# TestA.net
KiCad netlist of a schematic drawn in EAGLE
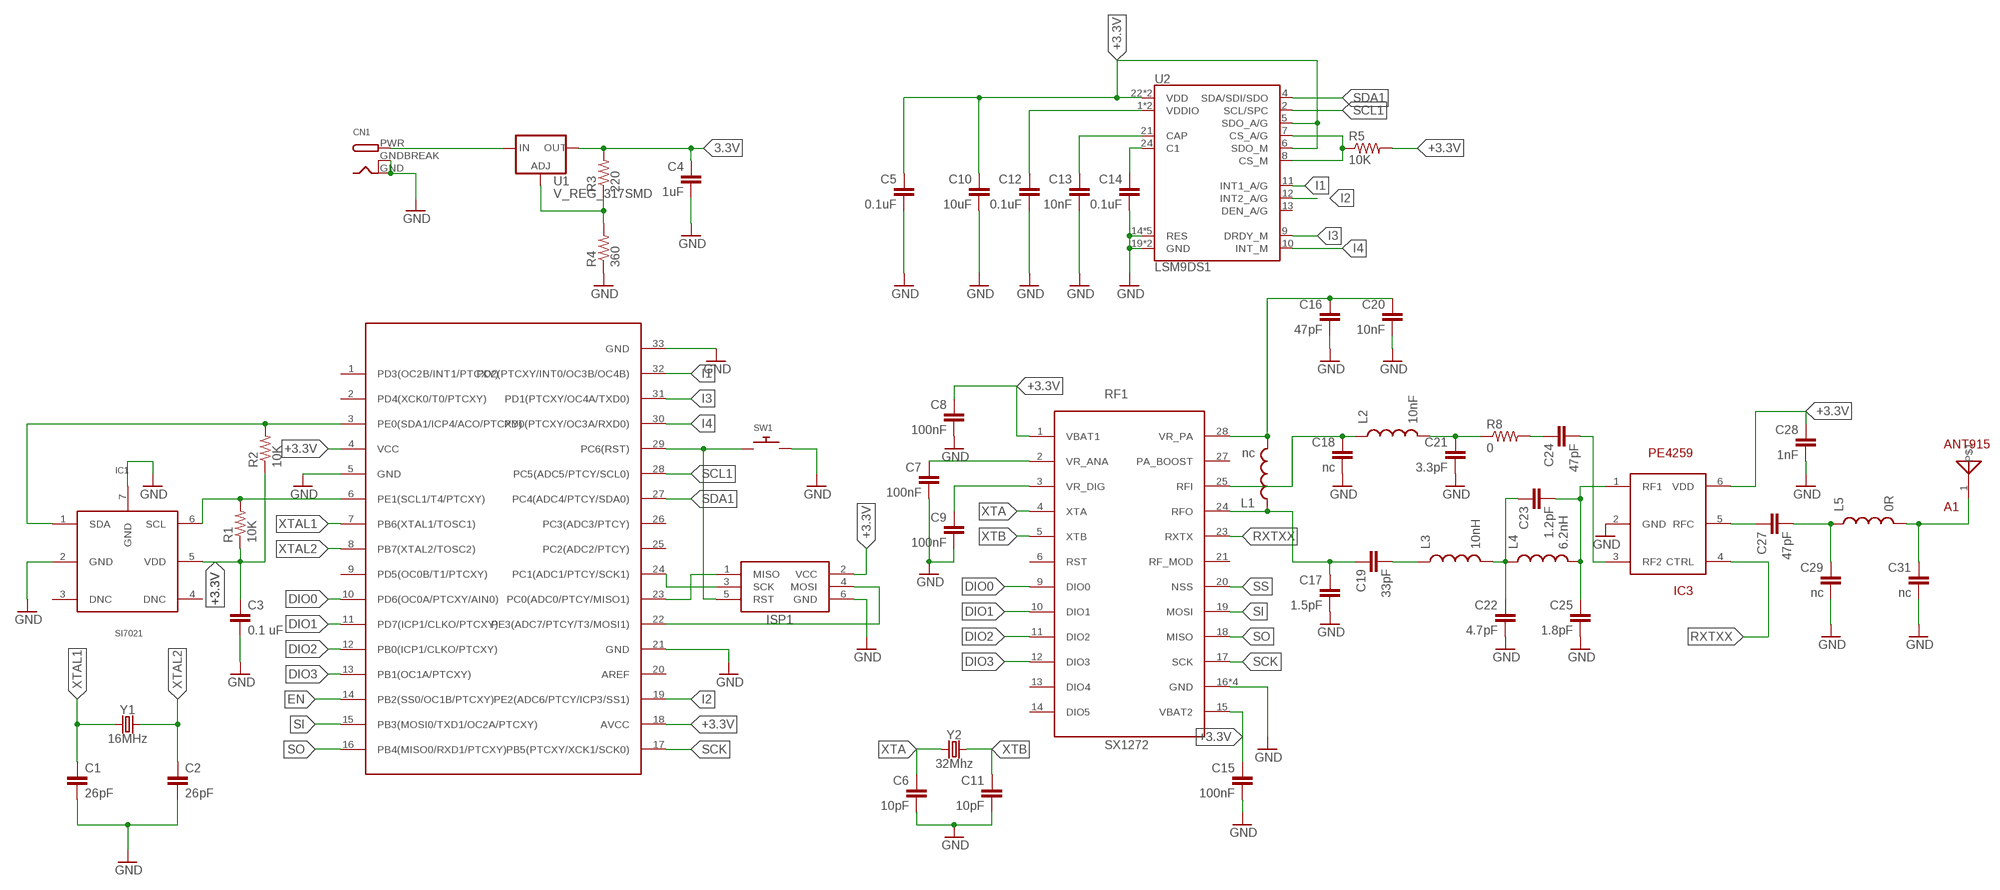
[diagram p0: schematic, sheet 1]

(export (version "E")
  (design (tool "Eeschema 10.0.6"))
  (components
    (comp (ref "A1")
      (value "ANT915")
      (footprint "eagle-import:ANT915")
      (libsource (lib "eagle-import") (part "ANT915"))
    )
    (comp (ref "C1")
      (value "26pF")
      (footprint "eagle-import:0402-CAP")
      (libsource (lib "eagle-import") (part "CAP0402-CAP"))
    )
    (comp (ref "C2")
      (value "26pF")
      (footprint "eagle-import:0402-CAP")
      (libsource (lib "eagle-import") (part "CAP0402-CAP"))
    )
    (comp (ref "C3")
      (value "0.1 uF")
      (footprint "eagle-import:0402-CAP")
      (libsource (lib "eagle-import") (part "CAP0402-CAP"))
    )
    (comp (ref "C4")
      (value "1uF")
      (footprint "eagle-import:0402-CAP")
      (libsource (lib "eagle-import") (part "CAP0402-CAP"))
    )
    (comp (ref "C5")
      (value "0.1uF")
      (footprint "eagle-import:0402-CAP")
      (libsource (lib "eagle-import") (part "CAP0402-CAP"))
    )
    (comp (ref "C6")
      (value "10pF")
      (footprint "eagle-import:0402-CAP")
      (libsource (lib "eagle-import") (part "CAP0402-CAP"))
    )
    (comp (ref "C7")
      (value "100nF")
      (footprint "eagle-import:0402-CAP")
      (libsource (lib "eagle-import") (part "CAP0402-CAP"))
    )
    (comp (ref "C8")
      (value "100nF")
      (footprint "eagle-import:0402-CAP")
      (libsource (lib "eagle-import") (part "CAP0402-CAP"))
    )
    (comp (ref "C9")
      (value "100nF")
      (footprint "eagle-import:0402-CAP")
      (libsource (lib "eagle-import") (part "CAP0402-CAP"))
    )
    (comp (ref "C10")
      (value "10uF")
      (footprint "eagle-import:0402-CAP")
      (libsource (lib "eagle-import") (part "CAP0402-CAP"))
    )
    (comp (ref "C11")
      (value "10pF")
      (footprint "eagle-import:0402-CAP")
      (libsource (lib "eagle-import") (part "CAP0402-CAP"))
    )
    (comp (ref "C12")
      (value "0.1uF")
      (footprint "eagle-import:0402-CAP")
      (libsource (lib "eagle-import") (part "CAP0402-CAP"))
    )
    (comp (ref "C13")
      (value "10nF")
      (footprint "eagle-import:0402-CAP")
      (libsource (lib "eagle-import") (part "CAP0402-CAP"))
    )
    (comp (ref "C14")
      (value "0.1uF")
      (footprint "eagle-import:0402-CAP")
      (libsource (lib "eagle-import") (part "CAP0402-CAP"))
    )
    (comp (ref "C15")
      (value "100nF")
      (footprint "eagle-import:0402-CAP")
      (libsource (lib "eagle-import") (part "CAP0402-CAP"))
    )
    (comp (ref "C16")
      (value "47pF")
      (footprint "eagle-import:0402-CAP")
      (libsource (lib "eagle-import") (part "CAP0402-CAP"))
    )
    (comp (ref "C17")
      (value "1.5pF")
      (footprint "eagle-import:0402-CAP")
      (libsource (lib "eagle-import") (part "CAP0402-CAP"))
    )
    (comp (ref "C18")
      (value "nc")
      (footprint "eagle-import:0402-CAP")
      (libsource (lib "eagle-import") (part "CAP0402-CAP"))
    )
    (comp (ref "C19")
      (value "33pF")
      (footprint "eagle-import:0402-CAP")
      (libsource (lib "eagle-import") (part "CAP0402-CAP"))
    )
    (comp (ref "C20")
      (value "10nF")
      (footprint "eagle-import:0402-CAP")
      (libsource (lib "eagle-import") (part "CAP0402-CAP"))
    )
    (comp (ref "C21")
      (value "3.3pF")
      (footprint "eagle-import:0402-CAP")
      (libsource (lib "eagle-import") (part "CAP0402-CAP"))
    )
    (comp (ref "C22")
      (value "4.7pF")
      (footprint "eagle-import:0402-CAP")
      (libsource (lib "eagle-import") (part "CAP0402-CAP"))
    )
    (comp (ref "C23")
      (value "1.2pF")
      (footprint "eagle-import:0402-CAP")
      (libsource (lib "eagle-import") (part "CAP0402-CAP"))
    )
    (comp (ref "C24")
      (value "47pF")
      (footprint "eagle-import:0402-CAP")
      (libsource (lib "eagle-import") (part "CAP0402-CAP"))
    )
    (comp (ref "C25")
      (value "1.8pF")
      (footprint "eagle-import:0402-CAP")
      (libsource (lib "eagle-import") (part "CAP0402-CAP"))
    )
    (comp (ref "C27")
      (value "47pF")
      (footprint "eagle-import:0402-CAP")
      (libsource (lib "eagle-import") (part "CAP0402-CAP"))
    )
    (comp (ref "C28")
      (value "1nF")
      (footprint "eagle-import:0402-CAP")
      (libsource (lib "eagle-import") (part "CAP0402-CAP"))
    )
    (comp (ref "C29")
      (value "nc")
      (footprint "eagle-import:0402-CAP")
      (libsource (lib "eagle-import") (part "CAP0402-CAP"))
    )
    (comp (ref "C31")
      (value "nc")
      (footprint "eagle-import:0402-CAP")
      (libsource (lib "eagle-import") (part "CAP0402-CAP"))
    )
    (comp (ref "CN1")
      (value "DCBARRELPTH")
      (footprint "eagle-import:DCJACK_2MM_PTH")
      (libsource (lib "eagle-import") (part "DCBARRELPTH"))
    )
    (comp (ref "IC1")
      (value "SI7021")
      (footprint "eagle-import:SI7021")
      (libsource (lib "eagle-import") (part "SI7021"))
    )
    (comp (ref "IC2")
      (value "ATMEGA328-PB")
      (footprint "eagle-import:ATMEGA328-PB")
      (libsource (lib "eagle-import") (part "ATMEGA328-PB"))
    )
    (comp (ref "IC3")
      (value "PE4259")
      (footprint "eagle-import:PE4259")
      (libsource (lib "eagle-import") (part "PE4259"))
    )
    (comp (ref "ISP1")
      (value "AVRISP-6")
      (footprint "eagle-import:AVRISP")
      (libsource (lib "eagle-import") (part "AVRISP-6"))
    )
    (comp (ref "L1")
      (value "nc")
      (footprint "eagle-import:C0402")
      (libsource (lib "eagle-import") (part "INDUCTOR0402"))
    )
    (comp (ref "L2")
      (value "10nF")
      (footprint "eagle-import:C0402")
      (libsource (lib "eagle-import") (part "INDUCTOR0402"))
    )
    (comp (ref "L3")
      (value "10nH")
      (footprint "eagle-import:C0402")
      (libsource (lib "eagle-import") (part "INDUCTOR0402"))
    )
    (comp (ref "L4")
      (value "6.2nH")
      (footprint "eagle-import:C0402")
      (libsource (lib "eagle-import") (part "INDUCTOR0402"))
    )
    (comp (ref "L5")
      (value "0R")
      (footprint "eagle-import:C0402")
      (libsource (lib "eagle-import") (part "INDUCTOR0402"))
    )
    (comp (ref "R1")
      (value "10K")
      (footprint "eagle-import:0402-RES")
      (libsource (lib "eagle-import") (part "RESISTOR0402-RES"))
    )
    (comp (ref "R2")
      (value "10K")
      (footprint "eagle-import:0402-RES")
      (libsource (lib "eagle-import") (part "RESISTOR0402-RES"))
    )
    (comp (ref "R3")
      (value "220")
      (footprint "eagle-import:0402-RES")
      (libsource (lib "eagle-import") (part "RESISTOR0402-RES"))
    )
    (comp (ref "R4")
      (value "360")
      (footprint "eagle-import:0402-RES")
      (libsource (lib "eagle-import") (part "RESISTOR0402-RES"))
    )
    (comp (ref "R5")
      (value "10K")
      (footprint "eagle-import:0402-RES")
      (libsource (lib "eagle-import") (part "RESISTOR0402-RES"))
    )
    (comp (ref "R8")
      (value "0")
      (footprint "eagle-import:0402-RES")
      (libsource (lib "eagle-import") (part "RESISTOR0402-RES"))
    )
    (comp (ref "RF1")
      (value "SX1272")
      (footprint "eagle-import:SX1272")
      (libsource (lib "eagle-import") (part "SX1272"))
    )
    (comp (ref "SW1")
      (value "SWITCH_PUSHBUTTONSOFTTOUCHSMD_SJ")
      (footprint "eagle-import:PUSHBUTTON_SMD_SJ")
      (libsource (lib "eagle-import") (part "SWITCH_PUSHBUTTONSOFTTOUCHSMD_SJ"))
    )
    (comp (ref "U1")
      (value "V_REG_317SMD")
      (footprint "eagle-import:SOT223")
      (libsource (lib "eagle-import") (part "V_REG_317SMD"))
    )
    (comp (ref "U2")
      (value "LSM9DS1")
      (footprint "eagle-import:LGA24-8X4")
      (libsource (lib "eagle-import") (part "LSM9DS1"))
    )
    (comp (ref "Y1")
      (value "16MHz")
      (footprint "eagle-import:CRYSTAL-SMD-2.0X1.6MM")
      (libsource (lib "eagle-import") (part "CRYSTAL-16MHZSMD-2X1.6"))
    )
    (comp (ref "Y2")
      (value "32Mhz")
      (footprint "eagle-import:CRYSTAL-SMD-2.0X1.6MM")
      (libsource (lib "eagle-import") (part "CRYSTAL-16MHZSMD-2X1.6"))
    )
  )
  (nets
    (net (code "1") (name "+3.3V") (class "Default")
      (node (ref "C10") (pin "1") (pinfunction "1_1") (pintype "passive"))
      (node (ref "C15") (pin "1") (pinfunction "1_1") (pintype "passive"))
      (node (ref "C28") (pin "1") (pinfunction "1_1") (pintype "passive"))
      (node (ref "C3") (pin "1") (pinfunction "1_1") (pintype "passive"))
      (node (ref "C5") (pin "1") (pinfunction "1_1") (pintype "passive"))
      (node (ref "C8") (pin "1") (pinfunction "1_1") (pintype "passive"))
      (node (ref "IC1") (pin "5") (pinfunction "VDD_5") (pintype "bidirectional"))
      (node (ref "IC2") (pin "18") (pinfunction "AVCC_18") (pintype "bidirectional"))
      (node (ref "IC2") (pin "4") (pinfunction "VCC_4") (pintype "bidirectional"))
      (node (ref "IC3") (pin "6") (pinfunction "VDD_6") (pintype "bidirectional"))
      (node (ref "ISP1") (pin "2") (pinfunction "VCC_2") (pintype "power_in"))
      (node (ref "R1") (pin "1") (pinfunction "1_1") (pintype "passive"))
      (node (ref "R2") (pin "1") (pinfunction "1_1") (pintype "passive"))
      (node (ref "R5") (pin "2") (pinfunction "2_2") (pintype "passive"))
      (node (ref "RF1") (pin "1") (pinfunction "VBAT1_1") (pintype "bidirectional"))
      (node (ref "RF1") (pin "15") (pinfunction "VBAT2_15") (pintype "bidirectional"))
      (node (ref "U2") (pin "22") (pinfunction "VDD_22") (pintype "bidirectional"))
      (node (ref "U2") (pin "23") (pinfunction "VDD_23") (pintype "bidirectional"))
      (node (ref "U2") (pin "5") (pinfunction "SDO_A/G_5") (pintype "bidirectional"))
      (node (ref "U2") (pin "6") (pinfunction "SDO_M_6") (pintype "bidirectional"))
    )
    (net (code "2") (name "3.3V") (class "Default")
      (node (ref "C4") (pin "1") (pinfunction "1_1") (pintype "passive"))
      (node (ref "R3") (pin "2") (pinfunction "2_2") (pintype "passive"))
      (node (ref "U1") (pin "2") (pinfunction "OUT_2") (pintype "output"))
    )
    (net (code "3") (name "DIO0") (class "Default")
      (node (ref "IC2") (pin "10") (pinfunction "PD6(OC0A/PTCXY/AIN0)_10") (pintype "bidirectional"))
      (node (ref "RF1") (pin "9") (pinfunction "DIO0_9") (pintype "bidirectional"))
    )
    (net (code "4") (name "DIO1") (class "Default")
      (node (ref "IC2") (pin "11") (pinfunction "PD7(ICP1/CLKO/PTCXY)_11") (pintype "bidirectional"))
      (node (ref "RF1") (pin "10") (pinfunction "DIO1_10") (pintype "bidirectional"))
    )
    (net (code "5") (name "DIO2") (class "Default")
      (node (ref "IC2") (pin "12") (pinfunction "PB0(ICP1/CLKO/PTCXY)_12") (pintype "bidirectional"))
      (node (ref "RF1") (pin "11") (pinfunction "DIO2_11") (pintype "bidirectional"))
    )
    (net (code "6") (name "DIO3") (class "Default")
      (node (ref "IC2") (pin "13") (pinfunction "PB1(OC1A/PTCXY)_13") (pintype "bidirectional"))
      (node (ref "RF1") (pin "12") (pinfunction "DIO3_12") (pintype "bidirectional"))
    )
    (net (code "7") (name "EN") (class "Default")
      (node (ref "IC2") (pin "14") (pinfunction "PB2(SS0/OC1B/PTCXY)_14") (pintype "bidirectional"))
    )
    (net (code "8") (name "GND") (class "Default")
      (node (ref "C1") (pin "2") (pinfunction "2_2") (pintype "passive"))
      (node (ref "C10") (pin "2") (pinfunction "2_2") (pintype "passive"))
      (node (ref "C11") (pin "2") (pinfunction "2_2") (pintype "passive"))
      (node (ref "C12") (pin "2") (pinfunction "2_2") (pintype "passive"))
      (node (ref "C13") (pin "2") (pinfunction "2_2") (pintype "passive"))
      (node (ref "C14") (pin "2") (pinfunction "2_2") (pintype "passive"))
      (node (ref "C15") (pin "2") (pinfunction "2_2") (pintype "passive"))
      (node (ref "C16") (pin "2") (pinfunction "2_2") (pintype "passive"))
      (node (ref "C17") (pin "2") (pinfunction "2_2") (pintype "passive"))
      (node (ref "C18") (pin "2") (pinfunction "2_2") (pintype "passive"))
      (node (ref "C2") (pin "2") (pinfunction "2_2") (pintype "passive"))
      (node (ref "C20") (pin "2") (pinfunction "2_2") (pintype "passive"))
      (node (ref "C21") (pin "2") (pinfunction "2_2") (pintype "passive"))
      (node (ref "C22") (pin "2") (pinfunction "2_2") (pintype "passive"))
      (node (ref "C25") (pin "2") (pinfunction "2_2") (pintype "passive"))
      (node (ref "C28") (pin "2") (pinfunction "2_2") (pintype "passive"))
      (node (ref "C29") (pin "2") (pinfunction "2_2") (pintype "passive"))
      (node (ref "C3") (pin "2") (pinfunction "2_2") (pintype "passive"))
      (node (ref "C31") (pin "2") (pinfunction "2_2") (pintype "passive"))
      (node (ref "C4") (pin "2") (pinfunction "2_2") (pintype "passive"))
      (node (ref "C5") (pin "2") (pinfunction "2_2") (pintype "passive"))
      (node (ref "C6") (pin "2") (pinfunction "2_2") (pintype "passive"))
      (node (ref "C7") (pin "2") (pinfunction "2_2") (pintype "passive"))
      (node (ref "C8") (pin "2") (pinfunction "2_2") (pintype "passive"))
      (node (ref "C9") (pin "2") (pinfunction "2_2") (pintype "passive"))
      (node (ref "CN1") (pin "GND") (pinfunction "GND_GND") (pintype "power_in"))
      (node (ref "CN1") (pin "GNDBREAK") (pinfunction "GNDBREAK_GNDBREAK") (pintype "power_in"))
      (node (ref "IC1") (pin "2") (pinfunction "GND_2") (pintype "bidirectional"))
      (node (ref "IC1") (pin "7") (pinfunction "GND_7") (pintype "bidirectional"))
      (node (ref "IC2") (pin "21") (pinfunction "GND_21") (pintype "bidirectional"))
      (node (ref "IC2") (pin "33") (pinfunction "GND_33") (pintype "bidirectional"))
      (node (ref "IC2") (pin "5") (pinfunction "GND_5") (pintype "bidirectional"))
      (node (ref "IC3") (pin "2") (pinfunction "GND_2") (pintype "bidirectional"))
      (node (ref "ISP1") (pin "6") (pinfunction "GND_6") (pintype "power_in"))
      (node (ref "R4") (pin "1") (pinfunction "1_1") (pintype "passive"))
      (node (ref "RF1") (pin "16") (pinfunction "GND_16") (pintype "bidirectional"))
      (node (ref "RF1") (pin "22") (pinfunction "GND_22") (pintype "bidirectional"))
      (node (ref "RF1") (pin "26") (pinfunction "GND_26") (pintype "bidirectional"))
      (node (ref "RF1") (pin "29") (pinfunction "GND_29") (pintype "bidirectional"))
      (node (ref "SW1") (pin "P$2") (pinfunction "P$2_P$2") (pintype "passive"))
      (node (ref "U2") (pin "14") (pinfunction "RES_14") (pintype "bidirectional"))
      (node (ref "U2") (pin "15") (pinfunction "RES_15") (pintype "bidirectional"))
      (node (ref "U2") (pin "16") (pinfunction "RES_16") (pintype "bidirectional"))
      (node (ref "U2") (pin "17") (pinfunction "RES_17") (pintype "bidirectional"))
      (node (ref "U2") (pin "18") (pinfunction "RES_18") (pintype "bidirectional"))
      (node (ref "U2") (pin "19") (pinfunction "GND_19") (pintype "bidirectional"))
      (node (ref "U2") (pin "20") (pinfunction "GND_20") (pintype "bidirectional"))
    )
    (net (code "9") (name "I1") (class "Default")
      (node (ref "IC2") (pin "32") (pinfunction "PD2(PTCXY/INT0/OC3B/OC4B)_32") (pintype "bidirectional"))
      (node (ref "U2") (pin "11") (pinfunction "INT1_A/G_11") (pintype "bidirectional"))
    )
    (net (code "10") (name "I2") (class "Default")
      (node (ref "IC2") (pin "19") (pinfunction "PE2(ADC6/PTCY/ICP3/SS1)_19") (pintype "bidirectional"))
      (node (ref "U2") (pin "12") (pinfunction "INT2_A/G_12") (pintype "bidirectional"))
    )
    (net (code "11") (name "I3") (class "Default")
      (node (ref "IC2") (pin "31") (pinfunction "PD1(PTCXY/OC4A/TXD0)_31") (pintype "bidirectional"))
      (node (ref "U2") (pin "9") (pinfunction "DRDY_M_9") (pintype "bidirectional"))
    )
    (net (code "12") (name "I4") (class "Default")
      (node (ref "IC2") (pin "30") (pinfunction "PD0(PTCXY/OC3A/RXD0)_30") (pintype "bidirectional"))
      (node (ref "U2") (pin "10") (pinfunction "INT_M_10") (pintype "bidirectional"))
    )
    (net (code "13") (name "Net-(A1-P$1)") (class "Default")
      (node (ref "A1") (pin "1") (pinfunction "P$1_1") (pintype "bidirectional"))
      (node (ref "C31") (pin "1") (pinfunction "1_1") (pintype "passive"))
      (node (ref "L5") (pin "2") (pinfunction "2_2") (pintype "passive"))
    )
    (net (code "14") (name "Net-(C12-Pad1)") (class "Default")
      (node (ref "C12") (pin "1") (pinfunction "1_1") (pintype "passive"))
      (node (ref "U2") (pin "1") (pinfunction "VDDIO_1") (pintype "bidirectional"))
      (node (ref "U2") (pin "3") (pinfunction "VDDIO_3") (pintype "bidirectional"))
    )
    (net (code "15") (name "Net-(C19-Pad2)") (class "Default")
      (node (ref "C19") (pin "2") (pinfunction "2_2") (pintype "passive"))
      (node (ref "L3") (pin "1") (pinfunction "1_1") (pintype "passive"))
    )
    (net (code "16") (name "Net-(C21-Pad1)") (class "Default")
      (node (ref "C21") (pin "1") (pinfunction "1_1") (pintype "passive"))
      (node (ref "L2") (pin "2") (pinfunction "2_2") (pintype "passive"))
      (node (ref "R8") (pin "1") (pinfunction "1_1") (pintype "passive"))
    )
    (net (code "17") (name "Net-(C22-Pad1)") (class "Default")
      (node (ref "C22") (pin "1") (pinfunction "1_1") (pintype "passive"))
      (node (ref "C23") (pin "1") (pinfunction "1_1") (pintype "passive"))
      (node (ref "L3") (pin "2") (pinfunction "2_2") (pintype "passive"))
      (node (ref "L4") (pin "1") (pinfunction "1_1") (pintype "passive"))
    )
    (net (code "18") (name "Net-(C24-Pad1)") (class "Default")
      (node (ref "C24") (pin "1") (pinfunction "1_1") (pintype "passive"))
      (node (ref "R8") (pin "2") (pinfunction "2_2") (pintype "passive"))
    )
    (net (code "19") (name "Net-(C27-Pad2)") (class "Default")
      (node (ref "C27") (pin "2") (pinfunction "2_2") (pintype "passive"))
      (node (ref "C29") (pin "1") (pinfunction "1_1") (pintype "passive"))
      (node (ref "L5") (pin "1") (pinfunction "1_1") (pintype "passive"))
    )
    (net (code "20") (name "Net-(IC1-SCL)") (class "Default")
      (node (ref "IC1") (pin "6") (pinfunction "SCL_6") (pintype "bidirectional"))
      (node (ref "IC2") (pin "6") (pinfunction "PE1(SCL1/T4/PTCXY)_6") (pintype "bidirectional"))
      (node (ref "R1") (pin "2") (pinfunction "2_2") (pintype "passive"))
    )
    (net (code "21") (name "Net-(IC1-SDA)") (class "Default")
      (node (ref "IC1") (pin "1") (pinfunction "SDA_1") (pintype "bidirectional"))
      (node (ref "IC2") (pin "3") (pinfunction "PE0(SDA1/ICP4/ACO/PTCXY)_3") (pintype "bidirectional"))
      (node (ref "R2") (pin "2") (pinfunction "2_2") (pintype "passive"))
    )
    (net (code "22") (name "Net-(IC2-PC0(ADC0{slash}PTCY{slash}MISO1))") (class "Default")
      (node (ref "IC2") (pin "23") (pinfunction "PC0(ADC0/PTCY/MISO1)_23") (pintype "bidirectional"))
      (node (ref "ISP1") (pin "1") (pinfunction "MISO_1") (pintype "input"))
    )
    (net (code "23") (name "Net-(IC2-PC1(ADC1{slash}PTCY{slash}SCK1))") (class "Default")
      (node (ref "IC2") (pin "24") (pinfunction "PC1(ADC1/PTCY/SCK1)_24") (pintype "bidirectional"))
      (node (ref "ISP1") (pin "3") (pinfunction "SCK_3") (pintype "output"))
    )
    (net (code "24") (name "Net-(IC2-PC6(RST))") (class "Default")
      (node (ref "IC2") (pin "29") (pinfunction "PC6(RST)_29") (pintype "bidirectional"))
      (node (ref "ISP1") (pin "5") (pinfunction "RST_5") (pintype "output"))
      (node (ref "SW1") (pin "P$1") (pinfunction "P$1_P$1") (pintype "passive"))
    )
    (net (code "25") (name "Net-(IC2-PE3(ADC7{slash}PTCY{slash}T3{slash}MOSI1))") (class "Default")
      (node (ref "IC2") (pin "22") (pinfunction "PE3(ADC7/PTCY/T3/MOSI1)_22") (pintype "bidirectional"))
      (node (ref "ISP1") (pin "4") (pinfunction "MOSI_4") (pintype "output"))
    )
    (net (code "26") (name "Net-(IC3-RF1)") (class "Default")
      (node (ref "C23") (pin "2") (pinfunction "2_2") (pintype "passive"))
      (node (ref "C25") (pin "1") (pinfunction "1_1") (pintype "passive"))
      (node (ref "IC3") (pin "1") (pinfunction "RF1_1") (pintype "bidirectional"))
      (node (ref "L4") (pin "2") (pinfunction "2_2") (pintype "passive"))
    )
    (net (code "27") (name "Net-(IC3-RF2)") (class "Default")
      (node (ref "C24") (pin "2") (pinfunction "2_2") (pintype "passive"))
      (node (ref "IC3") (pin "3") (pinfunction "RF2_3") (pintype "bidirectional"))
    )
    (net (code "28") (name "Net-(IC3-RFC)") (class "Default")
      (node (ref "C27") (pin "1") (pinfunction "1_1") (pintype "passive"))
      (node (ref "IC3") (pin "5") (pinfunction "RFC_5") (pintype "bidirectional"))
    )
    (net (code "29") (name "Net-(RF1-RFI)") (class "Default")
      (node (ref "C18") (pin "1") (pinfunction "1_1") (pintype "passive"))
      (node (ref "L2") (pin "1") (pinfunction "1_1") (pintype "passive"))
      (node (ref "RF1") (pin "25") (pinfunction "RFI_25") (pintype "bidirectional"))
    )
    (net (code "30") (name "Net-(RF1-RFO)") (class "Default")
      (node (ref "C17") (pin "1") (pinfunction "1_1") (pintype "passive"))
      (node (ref "C19") (pin "1") (pinfunction "1_1") (pintype "passive"))
      (node (ref "L1") (pin "1") (pinfunction "1_1") (pintype "passive"))
      (node (ref "RF1") (pin "24") (pinfunction "RFO_24") (pintype "bidirectional"))
    )
    (net (code "31") (name "Net-(RF1-VR_ANA)") (class "Default")
      (node (ref "C7") (pin "1") (pinfunction "1_1") (pintype "passive"))
      (node (ref "RF1") (pin "2") (pinfunction "VR_ANA_2") (pintype "bidirectional"))
    )
    (net (code "32") (name "Net-(RF1-VR_DIG)") (class "Default")
      (node (ref "C9") (pin "1") (pinfunction "1_1") (pintype "passive"))
      (node (ref "RF1") (pin "3") (pinfunction "VR_DIG_3") (pintype "bidirectional"))
    )
    (net (code "33") (name "Net-(RF1-VR_PA)") (class "Default")
      (node (ref "C16") (pin "1") (pinfunction "1_1") (pintype "passive"))
      (node (ref "C20") (pin "1") (pinfunction "1_1") (pintype "passive"))
      (node (ref "L1") (pin "2") (pinfunction "2_2") (pintype "passive"))
      (node (ref "RF1") (pin "28") (pinfunction "VR_PA_28") (pintype "bidirectional"))
    )
    (net (code "34") (name "Net-(U1-ADJ)") (class "Default")
      (node (ref "R3") (pin "1") (pinfunction "1_1") (pintype "passive"))
      (node (ref "R4") (pin "2") (pinfunction "2_2") (pintype "passive"))
      (node (ref "U1") (pin "1") (pinfunction "ADJ_1") (pintype "input"))
    )
    (net (code "35") (name "Net-(U1-IN)") (class "Default")
      (node (ref "CN1") (pin "PWR") (pinfunction "PWR_PWR") (pintype "power_in"))
      (node (ref "U1") (pin "3") (pinfunction "IN_3") (pintype "input"))
    )
    (net (code "36") (name "Net-(U2-C1)") (class "Default")
      (node (ref "C14") (pin "1") (pinfunction "1_1") (pintype "passive"))
      (node (ref "U2") (pin "24") (pinfunction "C1_24") (pintype "bidirectional"))
    )
    (net (code "37") (name "Net-(U2-CAP)") (class "Default")
      (node (ref "C13") (pin "1") (pinfunction "1_1") (pintype "passive"))
      (node (ref "U2") (pin "21") (pinfunction "CAP_21") (pintype "bidirectional"))
    )
    (net (code "38") (name "Net-(U2-CS_A{slash}G)") (class "Default")
      (node (ref "R5") (pin "1") (pinfunction "1_1") (pintype "passive"))
      (node (ref "U2") (pin "7") (pinfunction "CS_A/G_7") (pintype "bidirectional"))
      (node (ref "U2") (pin "8") (pinfunction "CS_M_8") (pintype "bidirectional"))
    )
    (net (code "39") (name "RXTXX") (class "Default")
      (node (ref "IC3") (pin "4") (pinfunction "CTRL_4") (pintype "bidirectional"))
      (node (ref "RF1") (pin "23") (pinfunction "RXTX_23") (pintype "bidirectional"))
    )
    (net (code "40") (name "SCK") (class "Default")
      (node (ref "IC2") (pin "17") (pinfunction "PB5(PTCXY/XCK1/SCK0)_17") (pintype "bidirectional"))
      (node (ref "RF1") (pin "17") (pinfunction "SCK_17") (pintype "bidirectional"))
    )
    (net (code "41") (name "SCL1") (class "Default")
      (node (ref "IC2") (pin "28") (pinfunction "PC5(ADC5/PTCY/SCL0)_28") (pintype "bidirectional"))
      (node (ref "U2") (pin "2") (pinfunction "SCL/SPC_2") (pintype "bidirectional"))
    )
    (net (code "42") (name "SDA1") (class "Default")
      (node (ref "IC2") (pin "27") (pinfunction "PC4(ADC4/PTCY/SDA0)_27") (pintype "bidirectional"))
      (node (ref "U2") (pin "4") (pinfunction "SDA/SDI/SDO_4") (pintype "bidirectional"))
    )
    (net (code "43") (name "SI") (class "Default")
      (node (ref "IC2") (pin "15") (pinfunction "PB3(MOSI0/TXD1/OC2A/PTCXY)_15") (pintype "bidirectional"))
      (node (ref "RF1") (pin "19") (pinfunction "MOSI_19") (pintype "bidirectional"))
    )
    (net (code "44") (name "SO") (class "Default")
      (node (ref "IC2") (pin "16") (pinfunction "PB4(MISO0/RXD1/PTCXY)_16") (pintype "bidirectional"))
      (node (ref "RF1") (pin "18") (pinfunction "MISO_18") (pintype "bidirectional"))
    )
    (net (code "45") (name "SS") (class "Default")
      (node (ref "RF1") (pin "20") (pinfunction "NSS_20") (pintype "bidirectional"))
    )
    (net (code "46") (name "XTA") (class "Default")
      (node (ref "C6") (pin "1") (pinfunction "1_1") (pintype "passive"))
      (node (ref "RF1") (pin "4") (pinfunction "XTA_4") (pintype "bidirectional"))
      (node (ref "Y2") (pin "1") (pinfunction "1_1") (pintype "passive"))
    )
    (net (code "47") (name "XTAL1") (class "Default")
      (node (ref "C1") (pin "1") (pinfunction "1_1") (pintype "passive"))
      (node (ref "IC2") (pin "7") (pinfunction "PB6(XTAL1/TOSC1)_7") (pintype "bidirectional"))
      (node (ref "Y1") (pin "1") (pinfunction "1_1") (pintype "passive"))
    )
    (net (code "48") (name "XTAL2") (class "Default")
      (node (ref "C2") (pin "1") (pinfunction "1_1") (pintype "passive"))
      (node (ref "IC2") (pin "8") (pinfunction "PB7(XTAL2/TOSC2)_8") (pintype "bidirectional"))
      (node (ref "Y1") (pin "3") (pinfunction "2_3") (pintype "passive"))
    )
    (net (code "49") (name "XTB") (class "Default")
      (node (ref "C11") (pin "1") (pinfunction "1_1") (pintype "passive"))
      (node (ref "RF1") (pin "5") (pinfunction "XTB_5") (pintype "bidirectional"))
      (node (ref "Y2") (pin "3") (pinfunction "2_3") (pintype "passive"))
    )
    (net (code "50") (name "unconnected-(IC1-DNC-Pad3)") (class "Default")
      (node (ref "IC1") (pin "3") (pinfunction "DNC_3") (pintype "bidirectional"))
    )
    (net (code "51") (name "unconnected-(IC1-DNC-Pad4)") (class "Default")
      (node (ref "IC1") (pin "4") (pinfunction "DNC_4") (pintype "bidirectional"))
    )
    (net (code "52") (name "unconnected-(IC2-AREF-Pad20)") (class "Default")
      (node (ref "IC2") (pin "20") (pinfunction "AREF_20") (pintype "bidirectional"))
    )
    (net (code "53") (name "unconnected-(IC2-PC2(ADC2{slash}PTCY)-Pad25)") (class "Default")
      (node (ref "IC2") (pin "25") (pinfunction "PC2(ADC2/PTCY)_25") (pintype "bidirectional"))
    )
    (net (code "54") (name "unconnected-(IC2-PC3(ADC3{slash}PTCY)-Pad26)") (class "Default")
      (node (ref "IC2") (pin "26") (pinfunction "PC3(ADC3/PTCY)_26") (pintype "bidirectional"))
    )
    (net (code "55") (name "unconnected-(IC2-PD3(OC2B{slash}INT1{slash}PTCXY)-Pad1)") (class "Default")
      (node (ref "IC2") (pin "1") (pinfunction "PD3(OC2B/INT1/PTCXY)_1") (pintype "bidirectional"))
    )
    (net (code "56") (name "unconnected-(IC2-PD4(XCK0{slash}T0{slash}PTCXY)-Pad2)") (class "Default")
      (node (ref "IC2") (pin "2") (pinfunction "PD4(XCK0/T0/PTCXY)_2") (pintype "bidirectional"))
    )
    (net (code "57") (name "unconnected-(IC2-PD5(OC0B{slash}T1{slash}PTCXY)-Pad9)") (class "Default")
      (node (ref "IC2") (pin "9") (pinfunction "PD5(OC0B/T1/PTCXY)_9") (pintype "bidirectional"))
    )
    (net (code "58") (name "unconnected-(RF1-DIO4-Pad13)") (class "Default")
      (node (ref "RF1") (pin "13") (pinfunction "DIO4_13") (pintype "bidirectional"))
    )
    (net (code "59") (name "unconnected-(RF1-DIO5-Pad14)") (class "Default")
      (node (ref "RF1") (pin "14") (pinfunction "DIO5_14") (pintype "bidirectional"))
    )
    (net (code "60") (name "unconnected-(RF1-PA_BOOST-Pad27)") (class "Default")
      (node (ref "RF1") (pin "27") (pinfunction "PA_BOOST_27") (pintype "bidirectional"))
    )
    (net (code "61") (name "unconnected-(RF1-RF_MOD-Pad21)") (class "Default")
      (node (ref "RF1") (pin "21") (pinfunction "RF_MOD_21") (pintype "bidirectional"))
    )
    (net (code "62") (name "unconnected-(RF1-RST-Pad6)") (class "Default")
      (node (ref "RF1") (pin "6") (pinfunction "RST_6") (pintype "bidirectional"))
    )
    (net (code "63") (name "unconnected-(U2-DEN_A{slash}G-Pad13)") (class "Default")
      (node (ref "U2") (pin "13") (pinfunction "DEN_A/G_13") (pintype "bidirectional"))
    )
  )
)
